# MicroMod_Processor_Board-nRF52840.net
KiCad netlist of a schematic drawn in EAGLE
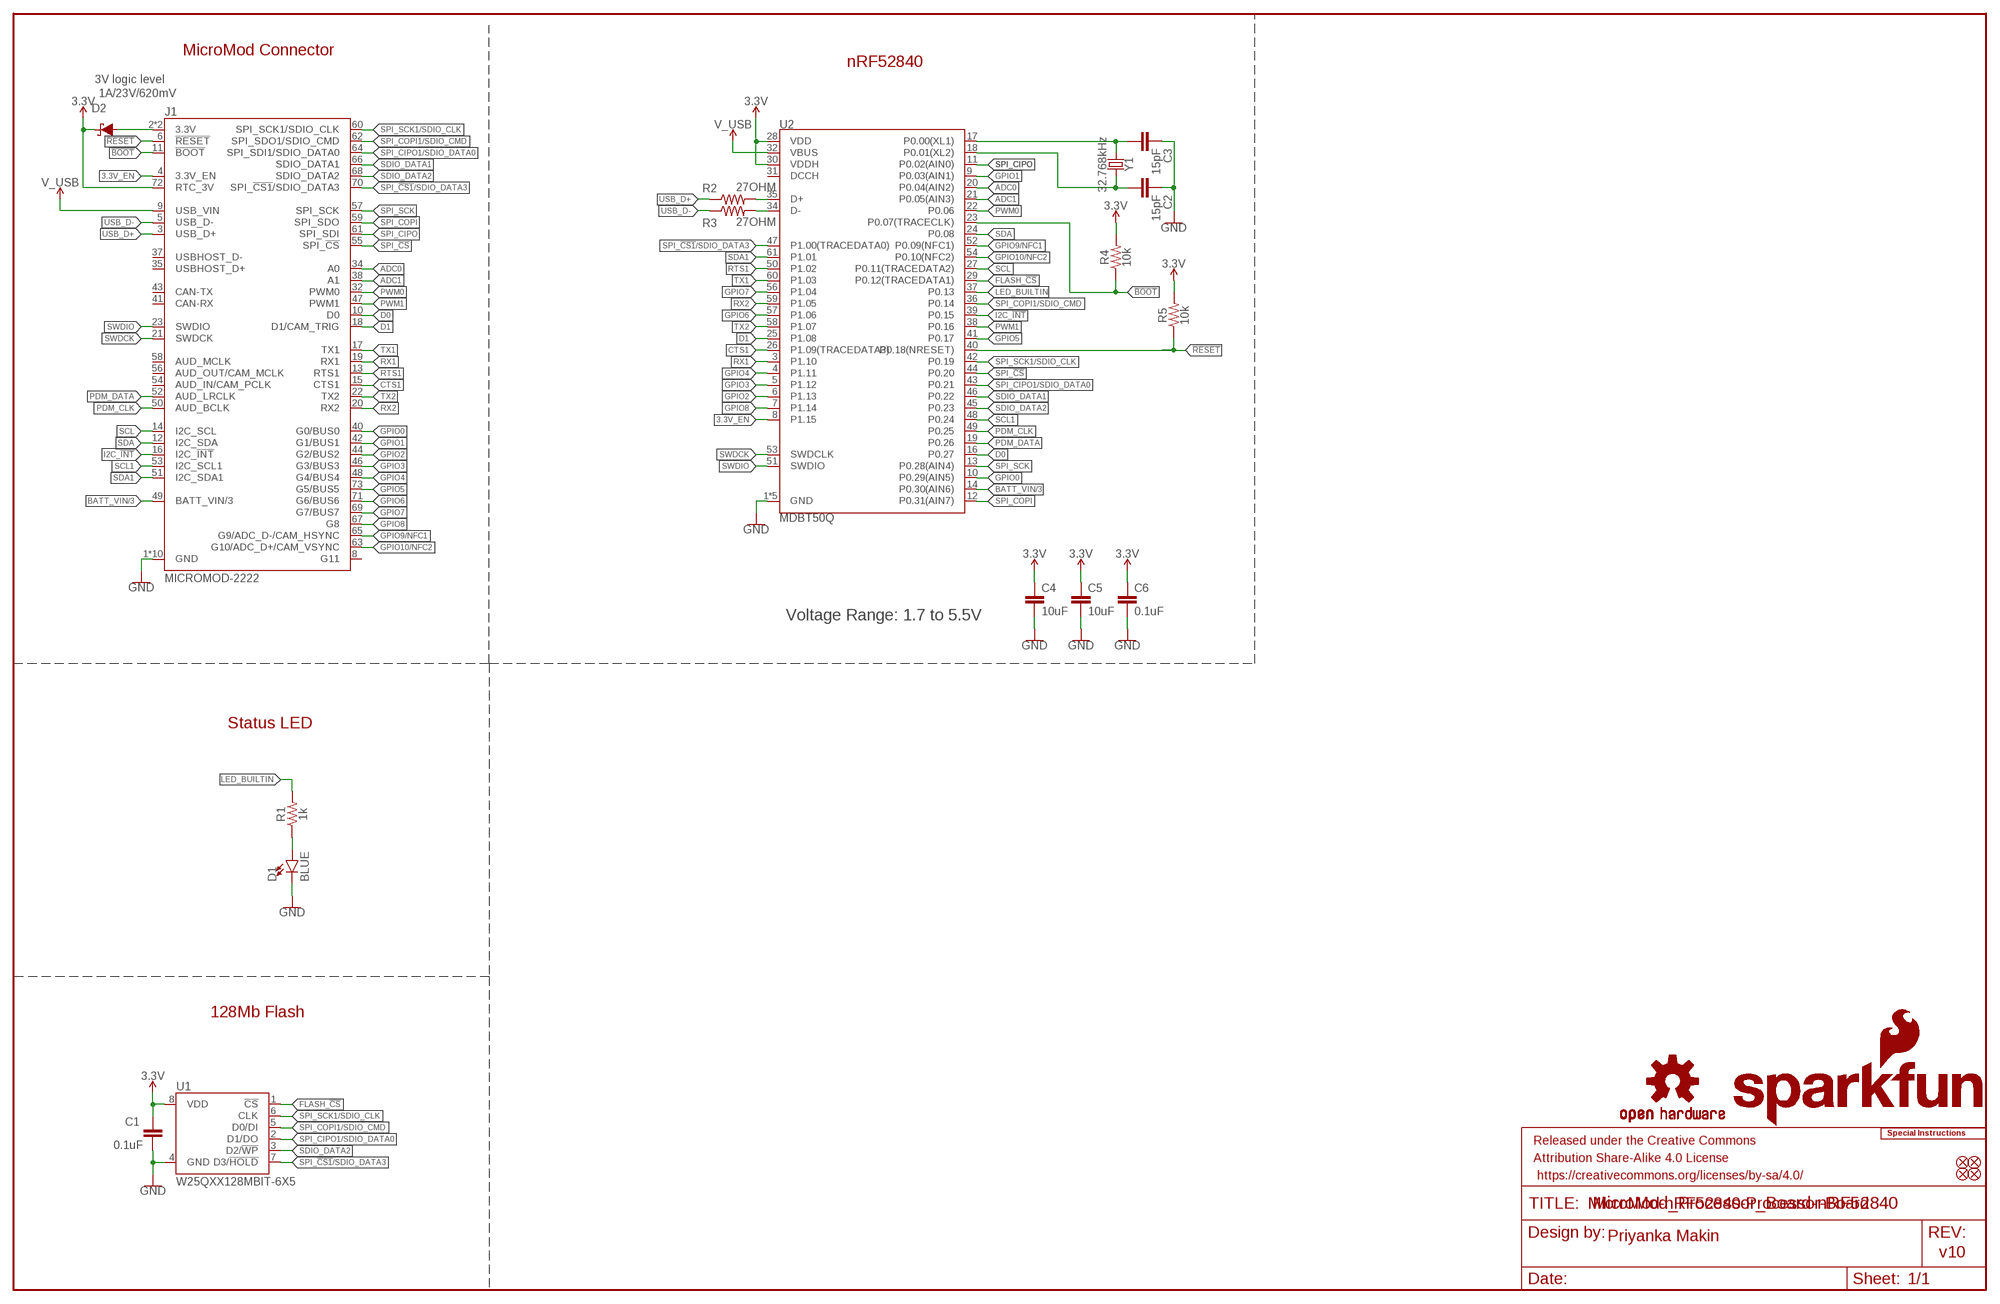
[diagram p0: schematic, sheet 1]

(export (version "E")
  (design (tool "Eeschema 10.0.6"))
  (components
    (comp (ref "C1")
      (value "0.1uF")
      (footprint "eagle-import:0402-TIGHT")
      (libsource (lib "eagle-import") (part "0.1UF-0402T-16V-10%"))
    )
    (comp (ref "C2")
      (value "15pF")
      (footprint "eagle-import:0402-TIGHT")
      (libsource (lib "eagle-import") (part "15PF-0402T-50V-5%"))
    )
    (comp (ref "C3")
      (value "15pF")
      (footprint "eagle-import:0402-TIGHT")
      (libsource (lib "eagle-import") (part "15PF-0402T-50V-5%"))
    )
    (comp (ref "C4")
      (value "10uF")
      (footprint "eagle-import:0402-TIGHT")
      (libsource (lib "eagle-import") (part "10UF-0402T-6.3V-20%"))
    )
    (comp (ref "C5")
      (value "10uF")
      (footprint "eagle-import:0402-TIGHT")
      (libsource (lib "eagle-import") (part "10UF-0402T-6.3V-20%"))
    )
    (comp (ref "C6")
      (value "0.1uF")
      (footprint "eagle-import:0402-TIGHT")
      (libsource (lib "eagle-import") (part "0.1UF-0402T-16V-10%"))
    )
    (comp (ref "D1")
      (value "BLUE")
      (footprint "eagle-import:LED-0603")
      (libsource (lib "eagle-import") (part "LED-BLUE0603"))
    )
    (comp (ref "D2")
      (value "1A/23V/620mV")
      (footprint "eagle-import:SOD-323")
      (libsource (lib "eagle-import") (part "DIODE-SCHOTTKY-BAT20J"))
    )
    (comp (ref "FD1")
      (value "FIDUCIALUFIDUCIAL")
      (footprint "eagle-import:FIDUCIAL-MICRO")
      (libsource (lib "eagle-import") (part "FIDUCIALUFIDUCIAL"))
    )
    (comp (ref "FD2")
      (value "FIDUCIALUFIDUCIAL")
      (footprint "eagle-import:FIDUCIAL-MICRO")
      (libsource (lib "eagle-import") (part "FIDUCIALUFIDUCIAL"))
    )
    (comp (ref "FD3")
      (value "FIDUCIALUFIDUCIAL")
      (footprint "eagle-import:FIDUCIAL-MICRO")
      (libsource (lib "eagle-import") (part "FIDUCIALUFIDUCIAL"))
    )
    (comp (ref "FD4")
      (value "FIDUCIALUFIDUCIAL")
      (footprint "eagle-import:FIDUCIAL-MICRO")
      (libsource (lib "eagle-import") (part "FIDUCIALUFIDUCIAL"))
    )
    (comp (ref "FRAME1")
      (value "FRAME-LEDGER")
      (footprint "eagle-import:CREATIVE_COMMONS")
      (libsource (lib "eagle-import") (part "FRAME-LEDGER"))
    )
    (comp (ref "J1")
      (value "MICROMOD-2222")
      (footprint "eagle-import:M.2-CARD-E-22")
      (libsource (lib "eagle-import") (part "MICROMOD-2222"))
    )
    (comp (ref "LOGO1")
      (value "SFE_LOGO_NAME_FLAME.1_INCH")
      (footprint "eagle-import:SFE_LOGO_NAME_FLAME_.1")
      (libsource (lib "eagle-import") (part "SFE_LOGO_NAME_FLAME.1_INCH"))
    )
    (comp (ref "LOGO2")
      (value "SFE_LOGO_FLAME.1_INCH")
      (footprint "eagle-import:SFE_LOGO_FLAME_.1")
      (libsource (lib "eagle-import") (part "SFE_LOGO_FLAME.1_INCH"))
    )
    (comp (ref "LOGO3")
      (value "OSHW-LOGOMINI")
      (footprint "eagle-import:OSHW-LOGO-MINI")
      (libsource (lib "eagle-import") (part "OSHW-LOGOMINI"))
    )
    (comp (ref "LOGO4")
      (value "SPECIAL_INSTRUCTIONS-ORDERING")
      (footprint "eagle-import:ORDERING_INSTRUCTIONS")
      (libsource (lib "eagle-import") (part "SPECIAL_INSTRUCTIONS-ORDERING"))
    )
    (comp (ref "R1")
      (value "1k")
      (footprint "eagle-import:0402-TIGHT")
      (libsource (lib "eagle-import") (part "1KOHM-0402T-1/16W-1%"))
    )
    (comp (ref "R2")
      (value "27OHM")
      (footprint "eagle-import:0402-TIGHT")
      (libsource (lib "eagle-import") (part "27OHM"))
    )
    (comp (ref "R3")
      (value "27OHM")
      (footprint "eagle-import:0402-TIGHT")
      (libsource (lib "eagle-import") (part "27OHM"))
    )
    (comp (ref "R4")
      (value "10k")
      (footprint "eagle-import:0402-TIGHT")
      (libsource (lib "eagle-import") (part "10KOHM-0402T-1/16W-1%"))
    )
    (comp (ref "R5")
      (value "10k")
      (footprint "eagle-import:0402-TIGHT")
      (libsource (lib "eagle-import") (part "10KOHM-0402T-1/16W-1%"))
    )
    (comp (ref "U1")
      (value "W25QXX128MBIT-6X5")
      (footprint "eagle-import:WSON-8-6X5")
      (libsource (lib "eagle-import") (part "W25QXX128MBIT-6X5"))
    )
    (comp (ref "U2")
      (value "MDBT50Q")
      (footprint "eagle-import:MDBT50Q")
      (libsource (lib "eagle-import") (part "MDBT50Q"))
    )
    (comp (ref "Y1")
      (value "32.768kHz")
      (footprint "eagle-import:CRYSTAL-SMD-3.2X1.5MM")
      (libsource (lib "eagle-import") (part "CRYSTAL-32.768KHZSMD-3.2X1.5"))
    )
  )
  (nets
    (net (code "1") (name "/FLASH_~{CS}") (class "Default")
      (node (ref "U1") (pin "1") (pinfunction "~{CS}_1") (pintype "bidirectional"))
      (node (ref "U2") (pin "29") (pinfunction "P0.12(TRACEDATA1)_29") (pintype "bidirectional"))
    )
    (net (code "2") (name "/I2C_~{INT}") (class "Default")
      (node (ref "J1") (pin "16") (pinfunction "I2C_~{INT}_16") (pintype "bidirectional"))
      (node (ref "U2") (pin "39") (pinfunction "P0.15_39") (pintype "bidirectional"))
    )
    (net (code "3") (name "/SPI_~{CS1}{slash}SDIO_DATA3") (class "Default")
      (node (ref "J1") (pin "70") (pinfunction "SPI_~{CS1}/SDIO_DATA3_70") (pintype "bidirectional"))
      (node (ref "U1") (pin "7") (pinfunction "D3/~{HOLD}_7") (pintype "bidirectional"))
      (node (ref "U2") (pin "47") (pinfunction "P1.00(TRACEDATA0)_47") (pintype "bidirectional"))
    )
    (net (code "4") (name "/SPI_~{CS}") (class "Default")
      (node (ref "J1") (pin "55") (pinfunction "SPI_~{CS}_55") (pintype "bidirectional"))
      (node (ref "U2") (pin "44") (pinfunction "P0.20_44") (pintype "bidirectional"))
    )
    (net (code "5") (name "/~{BOOT}") (class "Default")
      (node (ref "J1") (pin "11") (pinfunction "~{BOOT}_11") (pintype "bidirectional"))
      (node (ref "R4") (pin "1") (pinfunction "1_1") (pintype "passive"))
      (node (ref "U2") (pin "23") (pinfunction "P0.07(TRACECLK)_23") (pintype "bidirectional"))
    )
    (net (code "6") (name "/~{RESET}") (class "Default")
      (node (ref "J1") (pin "6") (pinfunction "~{RESET}_6") (pintype "bidirectional"))
      (node (ref "R5") (pin "1") (pinfunction "1_1") (pintype "passive"))
      (node (ref "U2") (pin "40") (pinfunction "P0.18(NRESET)_40") (pintype "bidirectional"))
    )
    (net (code "7") (name "3.3V") (class "Default")
      (node (ref "C1") (pin "1") (pinfunction "1_1") (pintype "passive"))
      (node (ref "C4") (pin "1") (pinfunction "1_1") (pintype "passive"))
      (node (ref "C5") (pin "1") (pinfunction "1_1") (pintype "passive"))
      (node (ref "C6") (pin "1") (pinfunction "1_1") (pintype "passive"))
      (node (ref "D2") (pin "C") (pinfunction "C_C") (pintype "passive"))
      (node (ref "J1") (pin "72") (pinfunction "RTC_3V_72") (pintype "bidirectional"))
      (node (ref "R4") (pin "2") (pinfunction "2_2") (pintype "passive"))
      (node (ref "R5") (pin "2") (pinfunction "2_2") (pintype "passive"))
      (node (ref "U1") (pin "8") (pinfunction "VDD_8") (pintype "bidirectional"))
      (node (ref "U2") (pin "28") (pinfunction "VDD_28") (pintype "bidirectional"))
      (node (ref "U2") (pin "30") (pinfunction "VDDH_30") (pintype "bidirectional"))
    )
    (net (code "8") (name "3.3V_EN") (class "Default")
      (node (ref "J1") (pin "4") (pinfunction "3.3V_EN_4") (pintype "bidirectional"))
      (node (ref "U2") (pin "8") (pinfunction "P1.15_8") (pintype "bidirectional"))
    )
    (net (code "9") (name "ADC0") (class "Default")
      (node (ref "J1") (pin "34") (pinfunction "A0_34") (pintype "bidirectional"))
      (node (ref "U2") (pin "20") (pinfunction "P0.04(AIN2)_20") (pintype "bidirectional"))
    )
    (net (code "10") (name "ADC1") (class "Default")
      (node (ref "J1") (pin "38") (pinfunction "A1_38") (pintype "bidirectional"))
      (node (ref "U2") (pin "21") (pinfunction "P0.05(AIN3)_21") (pintype "bidirectional"))
    )
    (net (code "11") (name "BATT_VIN{slash}3") (class "Default")
      (node (ref "J1") (pin "49") (pinfunction "BATT_VIN/3_49") (pintype "bidirectional"))
      (node (ref "U2") (pin "14") (pinfunction "P0.30(AIN6)_14") (pintype "bidirectional"))
    )
    (net (code "12") (name "CTS1") (class "Default")
      (node (ref "J1") (pin "15") (pinfunction "CTS1_15") (pintype "bidirectional"))
      (node (ref "U2") (pin "26") (pinfunction "P1.09(TRACEDATA3)_26") (pintype "bidirectional"))
    )
    (net (code "13") (name "D0") (class "Default")
      (node (ref "J1") (pin "10") (pinfunction "D0_10") (pintype "bidirectional"))
      (node (ref "U2") (pin "16") (pinfunction "P0.27_16") (pintype "bidirectional"))
    )
    (net (code "14") (name "D1") (class "Default")
      (node (ref "J1") (pin "18") (pinfunction "D1/CAM_TRIG_18") (pintype "bidirectional"))
      (node (ref "U2") (pin "25") (pinfunction "P1.08_25") (pintype "bidirectional"))
    )
    (net (code "15") (name "GND") (class "Default")
      (node (ref "C1") (pin "2") (pinfunction "2_2") (pintype "passive"))
      (node (ref "C2") (pin "1") (pinfunction "1_1") (pintype "passive"))
      (node (ref "C3") (pin "1") (pinfunction "1_1") (pintype "passive"))
      (node (ref "C4") (pin "2") (pinfunction "2_2") (pintype "passive"))
      (node (ref "C5") (pin "2") (pinfunction "2_2") (pintype "passive"))
      (node (ref "C6") (pin "2") (pinfunction "2_2") (pintype "passive"))
      (node (ref "D1") (pin "C") (pinfunction "C_C") (pintype "passive"))
      (node (ref "J1") (pin "1") (pinfunction "GND_1") (pintype "bidirectional"))
      (node (ref "J1") (pin "33") (pinfunction "GND_33") (pintype "bidirectional"))
      (node (ref "J1") (pin "36") (pinfunction "GND_36") (pintype "bidirectional"))
      (node (ref "J1") (pin "39") (pinfunction "GND_39") (pintype "bidirectional"))
      (node (ref "J1") (pin "45") (pinfunction "GND_45") (pintype "bidirectional"))
      (node (ref "J1") (pin "7") (pinfunction "GND_7") (pintype "bidirectional"))
      (node (ref "J1") (pin "75") (pinfunction "GND_75") (pintype "bidirectional"))
      (node (ref "J1") (pin "GND1") (pinfunction "GND_GND1") (pintype "bidirectional"))
      (node (ref "J1") (pin "GND2") (pinfunction "GND_GND2") (pintype "bidirectional"))
      (node (ref "J1") (pin "GND3") (pinfunction "GND_GND3") (pintype "bidirectional"))
      (node (ref "U1") (pin "4") (pinfunction "GND_4") (pintype "bidirectional"))
      (node (ref "U2") (pin "1") (pinfunction "GND_1") (pintype "bidirectional"))
      (node (ref "U2") (pin "15") (pinfunction "GND_15") (pintype "bidirectional"))
      (node (ref "U2") (pin "2") (pinfunction "GND_2") (pintype "bidirectional"))
      (node (ref "U2") (pin "33") (pinfunction "GND_33") (pintype "bidirectional"))
      (node (ref "U2") (pin "55") (pinfunction "GND_55") (pintype "bidirectional"))
    )
    (net (code "16") (name "GPIO0") (class "Default")
      (node (ref "J1") (pin "40") (pinfunction "G0/BUS0_40") (pintype "bidirectional"))
      (node (ref "U2") (pin "10") (pinfunction "P0.29(AIN5)_10") (pintype "bidirectional"))
    )
    (net (code "17") (name "GPIO1") (class "Default")
      (node (ref "J1") (pin "42") (pinfunction "G1/BUS1_42") (pintype "bidirectional"))
      (node (ref "U2") (pin "9") (pinfunction "P0.03(AIN1)_9") (pintype "bidirectional"))
    )
    (net (code "18") (name "GPIO2") (class "Default")
      (node (ref "J1") (pin "44") (pinfunction "G2/BUS2_44") (pintype "bidirectional"))
      (node (ref "U2") (pin "6") (pinfunction "P1.13_6") (pintype "bidirectional"))
    )
    (net (code "19") (name "GPIO3") (class "Default")
      (node (ref "J1") (pin "46") (pinfunction "G3/BUS3_46") (pintype "bidirectional"))
      (node (ref "U2") (pin "5") (pinfunction "P1.12_5") (pintype "bidirectional"))
    )
    (net (code "20") (name "GPIO4") (class "Default")
      (node (ref "J1") (pin "48") (pinfunction "G4/BUS4_48") (pintype "bidirectional"))
      (node (ref "U2") (pin "4") (pinfunction "P1.11_4") (pintype "bidirectional"))
    )
    (net (code "21") (name "GPIO5") (class "Default")
      (node (ref "J1") (pin "73") (pinfunction "G5/BUS5_73") (pintype "bidirectional"))
      (node (ref "U2") (pin "41") (pinfunction "P0.17_41") (pintype "bidirectional"))
    )
    (net (code "22") (name "GPIO6") (class "Default")
      (node (ref "J1") (pin "71") (pinfunction "G6/BUS6_71") (pintype "bidirectional"))
      (node (ref "U2") (pin "57") (pinfunction "P1.06_57") (pintype "bidirectional"))
    )
    (net (code "23") (name "GPIO7") (class "Default")
      (node (ref "J1") (pin "69") (pinfunction "G7/BUS7_69") (pintype "bidirectional"))
      (node (ref "U2") (pin "56") (pinfunction "P1.04_56") (pintype "bidirectional"))
    )
    (net (code "24") (name "GPIO8") (class "Default")
      (node (ref "J1") (pin "67") (pinfunction "G8_67") (pintype "bidirectional"))
      (node (ref "U2") (pin "7") (pinfunction "P1.14_7") (pintype "bidirectional"))
    )
    (net (code "25") (name "GPIO9{slash}NFC1") (class "Default")
      (node (ref "J1") (pin "65") (pinfunction "G9/ADC_D-/CAM_HSYNC_65") (pintype "bidirectional"))
      (node (ref "U2") (pin "52") (pinfunction "P0.09(NFC1)_52") (pintype "bidirectional"))
    )
    (net (code "26") (name "GPIO10{slash}NFC2") (class "Default")
      (node (ref "J1") (pin "63") (pinfunction "G10/ADC_D+/CAM_VSYNC_63") (pintype "bidirectional"))
      (node (ref "U2") (pin "54") (pinfunction "P0.10(NFC2)_54") (pintype "bidirectional"))
    )
    (net (code "27") (name "LED_BUILTIN") (class "Default")
      (node (ref "R1") (pin "2") (pinfunction "2_2") (pintype "passive"))
      (node (ref "U2") (pin "37") (pinfunction "P0.13_37") (pintype "bidirectional"))
    )
    (net (code "28") (name "Net-(D1-PadA)") (class "Default")
      (node (ref "D1") (pin "A") (pinfunction "A_A") (pintype "passive"))
      (node (ref "R1") (pin "1") (pinfunction "1_1") (pintype "passive"))
    )
    (net (code "29") (name "Net-(D2-PadA)") (class "Default")
      (node (ref "D2") (pin "A") (pinfunction "A_A") (pintype "passive"))
      (node (ref "J1") (pin "2") (pinfunction "3.3V_2") (pintype "bidirectional"))
      (node (ref "J1") (pin "74") (pinfunction "3.3V_74") (pintype "bidirectional"))
    )
    (net (code "30") (name "Net-(U2-D+)") (class "Default")
      (node (ref "R2") (pin "2") (pinfunction "2_2") (pintype "passive"))
      (node (ref "U2") (pin "35") (pinfunction "D+_35") (pintype "bidirectional"))
    )
    (net (code "31") (name "Net-(U2-D-)") (class "Default")
      (node (ref "R3") (pin "2") (pinfunction "2_2") (pintype "passive"))
      (node (ref "U2") (pin "34") (pinfunction "D-_34") (pintype "bidirectional"))
    )
    (net (code "32") (name "Net-(U2-P0.00(XL1))") (class "Default")
      (node (ref "C3") (pin "2") (pinfunction "2_2") (pintype "passive"))
      (node (ref "U2") (pin "17") (pinfunction "P0.00(XL1)_17") (pintype "bidirectional"))
      (node (ref "Y1") (pin "P$1") (pinfunction "1_P$1") (pintype "passive"))
    )
    (net (code "33") (name "Net-(U2-P0.01(XL2))") (class "Default")
      (node (ref "C2") (pin "2") (pinfunction "2_2") (pintype "passive"))
      (node (ref "U2") (pin "18") (pinfunction "P0.01(XL2)_18") (pintype "bidirectional"))
      (node (ref "Y1") (pin "P$2") (pinfunction "2_P$2") (pintype "passive"))
    )
    (net (code "34") (name "PDM_CLK") (class "Default")
      (node (ref "J1") (pin "50") (pinfunction "AUD_BCLK_50") (pintype "bidirectional"))
      (node (ref "U2") (pin "49") (pinfunction "P0.25_49") (pintype "bidirectional"))
    )
    (net (code "35") (name "PDM_DATA") (class "Default")
      (node (ref "J1") (pin "52") (pinfunction "AUD_LRCLK_52") (pintype "bidirectional"))
      (node (ref "U2") (pin "19") (pinfunction "P0.26_19") (pintype "bidirectional"))
    )
    (net (code "36") (name "PWM0") (class "Default")
      (node (ref "J1") (pin "32") (pinfunction "PWM0_32") (pintype "bidirectional"))
      (node (ref "U2") (pin "22") (pinfunction "P0.06_22") (pintype "bidirectional"))
    )
    (net (code "37") (name "PWM1") (class "Default")
      (node (ref "J1") (pin "47") (pinfunction "PWM1_47") (pintype "bidirectional"))
      (node (ref "U2") (pin "38") (pinfunction "P0.16_38") (pintype "bidirectional"))
    )
    (net (code "38") (name "RTS1") (class "Default")
      (node (ref "J1") (pin "13") (pinfunction "RTS1_13") (pintype "bidirectional"))
      (node (ref "U2") (pin "50") (pinfunction "P1.02_50") (pintype "bidirectional"))
    )
    (net (code "39") (name "RX1") (class "Default")
      (node (ref "J1") (pin "19") (pinfunction "RX1_19") (pintype "bidirectional"))
      (node (ref "U2") (pin "3") (pinfunction "P1.10_3") (pintype "bidirectional"))
    )
    (net (code "40") (name "RX2") (class "Default")
      (node (ref "J1") (pin "20") (pinfunction "RX2_20") (pintype "bidirectional"))
      (node (ref "U2") (pin "59") (pinfunction "P1.05_59") (pintype "bidirectional"))
    )
    (net (code "41") (name "SCL") (class "Default")
      (node (ref "J1") (pin "14") (pinfunction "I2C_SCL_14") (pintype "bidirectional"))
      (node (ref "U2") (pin "27") (pinfunction "P0.11(TRACEDATA2)_27") (pintype "bidirectional"))
    )
    (net (code "42") (name "SCL1") (class "Default")
      (node (ref "J1") (pin "53") (pinfunction "I2C_SCL1_53") (pintype "bidirectional"))
      (node (ref "U2") (pin "48") (pinfunction "P0.24_48") (pintype "bidirectional"))
    )
    (net (code "43") (name "SDA") (class "Default")
      (node (ref "J1") (pin "12") (pinfunction "I2C_SDA_12") (pintype "bidirectional"))
      (node (ref "U2") (pin "24") (pinfunction "P0.08_24") (pintype "bidirectional"))
    )
    (net (code "44") (name "SDA1") (class "Default")
      (node (ref "J1") (pin "51") (pinfunction "I2C_SDA1_51") (pintype "bidirectional"))
      (node (ref "U2") (pin "61") (pinfunction "P1.01_61") (pintype "bidirectional"))
    )
    (net (code "45") (name "SDIO_DATA1") (class "Default")
      (node (ref "J1") (pin "66") (pinfunction "SDIO_DATA1_66") (pintype "bidirectional"))
      (node (ref "U2") (pin "46") (pinfunction "P0.22_46") (pintype "bidirectional"))
    )
    (net (code "46") (name "SDIO_DATA2") (class "Default")
      (node (ref "J1") (pin "68") (pinfunction "SDIO_DATA2_68") (pintype "bidirectional"))
      (node (ref "U1") (pin "3") (pinfunction "D2/~{WP}_3") (pintype "bidirectional"))
      (node (ref "U2") (pin "45") (pinfunction "P0.23_45") (pintype "bidirectional"))
    )
    (net (code "47") (name "SPI_CIPO") (class "Default")
      (node (ref "J1") (pin "61") (pinfunction "SPI_SDI_61") (pintype "bidirectional"))
      (node (ref "U2") (pin "11") (pinfunction "P0.02(AIN0)_11") (pintype "bidirectional"))
    )
    (net (code "48") (name "SPI_CIPO1{slash}SDIO_DATA0") (class "Default")
      (node (ref "J1") (pin "64") (pinfunction "SPI_SDI1/SDIO_DATA0_64") (pintype "bidirectional"))
      (node (ref "U1") (pin "2") (pinfunction "D1/DO_2") (pintype "bidirectional"))
      (node (ref "U2") (pin "43") (pinfunction "P0.21_43") (pintype "bidirectional"))
    )
    (net (code "49") (name "SPI_COPI") (class "Default")
      (node (ref "J1") (pin "59") (pinfunction "SPI_SDO_59") (pintype "bidirectional"))
      (node (ref "U2") (pin "12") (pinfunction "P0.31(AIN7)_12") (pintype "bidirectional"))
    )
    (net (code "50") (name "SPI_COPI1{slash}SDIO_CMD") (class "Default")
      (node (ref "J1") (pin "62") (pinfunction "SPI_SDO1/SDIO_CMD_62") (pintype "bidirectional"))
      (node (ref "U1") (pin "5") (pinfunction "D0/DI_5") (pintype "bidirectional"))
      (node (ref "U2") (pin "36") (pinfunction "P0.14_36") (pintype "bidirectional"))
    )
    (net (code "51") (name "SPI_SCK") (class "Default")
      (node (ref "J1") (pin "57") (pinfunction "SPI_SCK_57") (pintype "bidirectional"))
      (node (ref "U2") (pin "13") (pinfunction "P0.28(AIN4)_13") (pintype "bidirectional"))
    )
    (net (code "52") (name "SPI_SCK1{slash}SDIO_CLK") (class "Default")
      (node (ref "J1") (pin "60") (pinfunction "SPI_SCK1/SDIO_CLK_60") (pintype "bidirectional"))
      (node (ref "U1") (pin "6") (pinfunction "CLK_6") (pintype "bidirectional"))
      (node (ref "U2") (pin "42") (pinfunction "P0.19_42") (pintype "bidirectional"))
    )
    (net (code "53") (name "SWDCK") (class "Default")
      (node (ref "J1") (pin "21") (pinfunction "SWDCK_21") (pintype "bidirectional"))
      (node (ref "U2") (pin "53") (pinfunction "SWDCLK_53") (pintype "bidirectional"))
    )
    (net (code "54") (name "SWDIO") (class "Default")
      (node (ref "J1") (pin "23") (pinfunction "SWDIO_23") (pintype "bidirectional"))
      (node (ref "U2") (pin "51") (pinfunction "SWDIO_51") (pintype "bidirectional"))
    )
    (net (code "55") (name "TX1") (class "Default")
      (node (ref "J1") (pin "17") (pinfunction "TX1_17") (pintype "bidirectional"))
      (node (ref "U2") (pin "60") (pinfunction "P1.03_60") (pintype "bidirectional"))
    )
    (net (code "56") (name "TX2") (class "Default")
      (node (ref "J1") (pin "22") (pinfunction "TX2_22") (pintype "bidirectional"))
      (node (ref "U2") (pin "58") (pinfunction "P1.07_58") (pintype "bidirectional"))
    )
    (net (code "57") (name "USB_D+") (class "Default")
      (node (ref "J1") (pin "3") (pinfunction "USB_D+_3") (pintype "bidirectional"))
      (node (ref "R2") (pin "1") (pinfunction "1_1") (pintype "passive"))
    )
    (net (code "58") (name "USB_D-") (class "Default")
      (node (ref "J1") (pin "5") (pinfunction "USB_D-_5") (pintype "bidirectional"))
      (node (ref "R3") (pin "1") (pinfunction "1_1") (pintype "passive"))
    )
    (net (code "59") (name "V_USB") (class "Default")
      (node (ref "J1") (pin "9") (pinfunction "USB_VIN_9") (pintype "bidirectional"))
      (node (ref "U2") (pin "32") (pinfunction "VBUS_32") (pintype "bidirectional"))
    )
    (net (code "60") (name "unconnected-(J1-AUD_IN{slash}CAM_PCLK-Pad54)") (class "Default")
      (node (ref "J1") (pin "54") (pinfunction "AUD_IN/CAM_PCLK_54") (pintype "bidirectional"))
    )
    (net (code "61") (name "unconnected-(J1-AUD_MCLK-Pad58)") (class "Default")
      (node (ref "J1") (pin "58") (pinfunction "AUD_MCLK_58") (pintype "bidirectional"))
    )
    (net (code "62") (name "unconnected-(J1-AUD_OUT{slash}CAM_MCLK-Pad56)") (class "Default")
      (node (ref "J1") (pin "56") (pinfunction "AUD_OUT/CAM_MCLK_56") (pintype "bidirectional"))
    )
    (net (code "63") (name "unconnected-(J1-CAN-RX-Pad41)") (class "Default")
      (node (ref "J1") (pin "41") (pinfunction "CAN-RX_41") (pintype "bidirectional"))
    )
    (net (code "64") (name "unconnected-(J1-CAN-TX-Pad43)") (class "Default")
      (node (ref "J1") (pin "43") (pinfunction "CAN-TX_43") (pintype "bidirectional"))
    )
    (net (code "65") (name "unconnected-(J1-G11-Pad8)") (class "Default")
      (node (ref "J1") (pin "8") (pinfunction "G11_8") (pintype "bidirectional"))
    )
    (net (code "66") (name "unconnected-(J1-USBHOST_D+-Pad35)") (class "Default")
      (node (ref "J1") (pin "35") (pinfunction "USBHOST_D+_35") (pintype "bidirectional"))
    )
    (net (code "67") (name "unconnected-(J1-USBHOST_D--Pad37)") (class "Default")
      (node (ref "J1") (pin "37") (pinfunction "USBHOST_D-_37") (pintype "bidirectional"))
    )
    (net (code "68") (name "unconnected-(U2-DCCH-Pad31)") (class "Default")
      (node (ref "U2") (pin "31") (pinfunction "DCCH_31") (pintype "bidirectional"))
    )
  )
)
